# Production_Solar_Array_Design.net
KiCad netlist of a schematic drawn in EAGLE
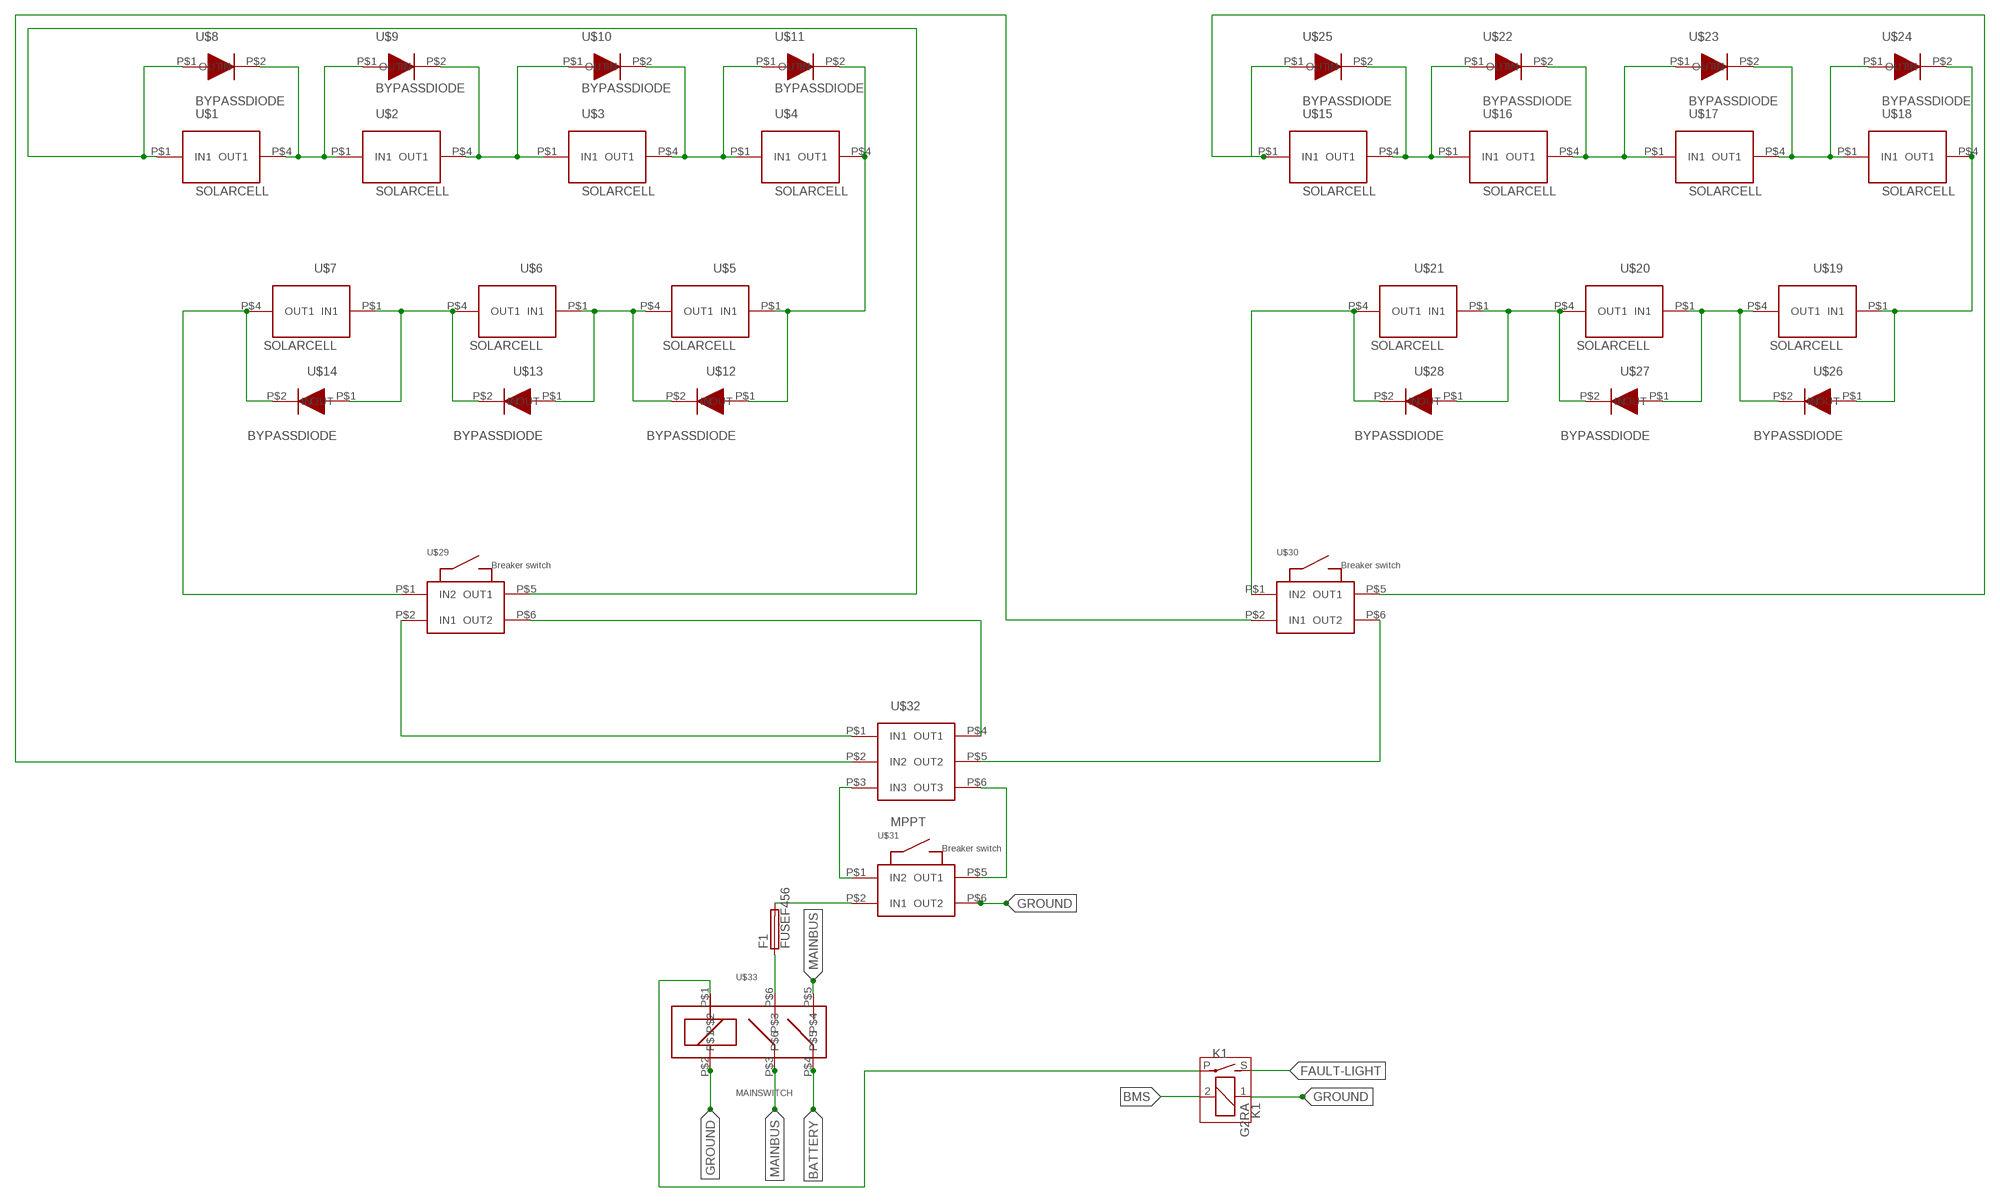
[diagram p0: schematic, sheet 1]

(export (version "E")
  (design (tool "Eeschema 10.0.6"))
  (components
    (comp (ref "F1")
      (value "FUSEF456")
      (footprint "eagle-import:F456")
      (libsource (lib "eagle-import") (part "FUSEF456"))
    )
    (comp (ref "K1")
      (value "G2RA")
      (footprint "eagle-import:G2RA")
      (libsource (lib "eagle-import") (part "G2RA"))
    )
    (comp (ref "U$1")
      (value "SOLARCELL")
      (footprint "eagle-import:SOLARCELL")
      (libsource (lib "eagle-import") (part "SOLARCELL"))
    )
    (comp (ref "U$2")
      (value "SOLARCELL")
      (footprint "eagle-import:SOLARCELL")
      (libsource (lib "eagle-import") (part "SOLARCELL"))
    )
    (comp (ref "U$3")
      (value "SOLARCELL")
      (footprint "eagle-import:SOLARCELL")
      (libsource (lib "eagle-import") (part "SOLARCELL"))
    )
    (comp (ref "U$4")
      (value "SOLARCELL")
      (footprint "eagle-import:SOLARCELL")
      (libsource (lib "eagle-import") (part "SOLARCELL"))
    )
    (comp (ref "U$5")
      (value "SOLARCELL")
      (footprint "eagle-import:SOLARCELL")
      (libsource (lib "eagle-import") (part "SOLARCELL"))
    )
    (comp (ref "U$6")
      (value "SOLARCELL")
      (footprint "eagle-import:SOLARCELL")
      (libsource (lib "eagle-import") (part "SOLARCELL"))
    )
    (comp (ref "U$7")
      (value "SOLARCELL")
      (footprint "eagle-import:SOLARCELL")
      (libsource (lib "eagle-import") (part "SOLARCELL"))
    )
    (comp (ref "U$8")
      (value "BYPASSDIODE")
      (footprint "eagle-import:BYPASSDIODE")
      (libsource (lib "eagle-import") (part "BYPASSDIODE"))
    )
    (comp (ref "U$9")
      (value "BYPASSDIODE")
      (footprint "eagle-import:BYPASSDIODE")
      (libsource (lib "eagle-import") (part "BYPASSDIODE"))
    )
    (comp (ref "U$10")
      (value "BYPASSDIODE")
      (footprint "eagle-import:BYPASSDIODE")
      (libsource (lib "eagle-import") (part "BYPASSDIODE"))
    )
    (comp (ref "U$11")
      (value "BYPASSDIODE")
      (footprint "eagle-import:BYPASSDIODE")
      (libsource (lib "eagle-import") (part "BYPASSDIODE"))
    )
    (comp (ref "U$12")
      (value "BYPASSDIODE")
      (footprint "eagle-import:BYPASSDIODE")
      (libsource (lib "eagle-import") (part "BYPASSDIODE"))
    )
    (comp (ref "U$13")
      (value "BYPASSDIODE")
      (footprint "eagle-import:BYPASSDIODE")
      (libsource (lib "eagle-import") (part "BYPASSDIODE"))
    )
    (comp (ref "U$14")
      (value "BYPASSDIODE")
      (footprint "eagle-import:BYPASSDIODE")
      (libsource (lib "eagle-import") (part "BYPASSDIODE"))
    )
    (comp (ref "U$15")
      (value "SOLARCELL")
      (footprint "eagle-import:SOLARCELL")
      (libsource (lib "eagle-import") (part "SOLARCELL"))
    )
    (comp (ref "U$16")
      (value "SOLARCELL")
      (footprint "eagle-import:SOLARCELL")
      (libsource (lib "eagle-import") (part "SOLARCELL"))
    )
    (comp (ref "U$17")
      (value "SOLARCELL")
      (footprint "eagle-import:SOLARCELL")
      (libsource (lib "eagle-import") (part "SOLARCELL"))
    )
    (comp (ref "U$18")
      (value "SOLARCELL")
      (footprint "eagle-import:SOLARCELL")
      (libsource (lib "eagle-import") (part "SOLARCELL"))
    )
    (comp (ref "U$19")
      (value "SOLARCELL")
      (footprint "eagle-import:SOLARCELL")
      (libsource (lib "eagle-import") (part "SOLARCELL"))
    )
    (comp (ref "U$20")
      (value "SOLARCELL")
      (footprint "eagle-import:SOLARCELL")
      (libsource (lib "eagle-import") (part "SOLARCELL"))
    )
    (comp (ref "U$21")
      (value "SOLARCELL")
      (footprint "eagle-import:SOLARCELL")
      (libsource (lib "eagle-import") (part "SOLARCELL"))
    )
    (comp (ref "U$22")
      (value "BYPASSDIODE")
      (footprint "eagle-import:BYPASSDIODE")
      (libsource (lib "eagle-import") (part "BYPASSDIODE"))
    )
    (comp (ref "U$23")
      (value "BYPASSDIODE")
      (footprint "eagle-import:BYPASSDIODE")
      (libsource (lib "eagle-import") (part "BYPASSDIODE"))
    )
    (comp (ref "U$24")
      (value "BYPASSDIODE")
      (footprint "eagle-import:BYPASSDIODE")
      (libsource (lib "eagle-import") (part "BYPASSDIODE"))
    )
    (comp (ref "U$25")
      (value "BYPASSDIODE")
      (footprint "eagle-import:BYPASSDIODE")
      (libsource (lib "eagle-import") (part "BYPASSDIODE"))
    )
    (comp (ref "U$26")
      (value "BYPASSDIODE")
      (footprint "eagle-import:BYPASSDIODE")
      (libsource (lib "eagle-import") (part "BYPASSDIODE"))
    )
    (comp (ref "U$27")
      (value "BYPASSDIODE")
      (footprint "eagle-import:BYPASSDIODE")
      (libsource (lib "eagle-import") (part "BYPASSDIODE"))
    )
    (comp (ref "U$28")
      (value "BYPASSDIODE")
      (footprint "eagle-import:BYPASSDIODE")
      (libsource (lib "eagle-import") (part "BYPASSDIODE"))
    )
    (comp (ref "U$29")
      (value "CIRCUITBREAKER")
      (footprint "eagle-import:CIRUITBREAKER")
      (libsource (lib "eagle-import") (part "CIRCUITBREAKER"))
    )
    (comp (ref "U$30")
      (value "CIRCUITBREAKER")
      (footprint "eagle-import:CIRUITBREAKER")
      (libsource (lib "eagle-import") (part "CIRCUITBREAKER"))
    )
    (comp (ref "U$31")
      (value "CIRCUITBREAKER")
      (footprint "eagle-import:CIRUITBREAKER")
      (libsource (lib "eagle-import") (part "CIRCUITBREAKER"))
    )
    (comp (ref "U$32")
      (value "MPPT")
      (footprint "eagle-import:MPPT")
      (libsource (lib "eagle-import") (part "MPPT"))
    )
    (comp (ref "U$33")
      (value "MAINSWITCH")
      (footprint "eagle-import:MAINSWITCH")
      (libsource (lib "eagle-import") (part "MAINSWITCH"))
    )
  )
  (nets
    (net (code "1") (name "BATTERY") (class "Default")
      (node (ref "U$33") (pin "P$4") (pinfunction "P$4_P$4") (pintype "bidirectional"))
    )
    (net (code "2") (name "BMS") (class "Default")
      (node (ref "K1") (pin "2") (pinfunction "2_2") (pintype "passive"))
    )
    (net (code "3") (name "FAULT-LIGHT") (class "Default")
      (node (ref "K1") (pin "S") (pinfunction "S_S") (pintype "passive"))
    )
    (net (code "4") (name "GROUND") (class "Default")
      (node (ref "K1") (pin "1") (pinfunction "1_1") (pintype "passive"))
      (node (ref "U$31") (pin "P$6") (pinfunction "OUT2_P$6") (pintype "bidirectional"))
      (node (ref "U$33") (pin "P$2") (pinfunction "P$2_P$2") (pintype "bidirectional"))
    )
    (net (code "5") (name "MAINBUS") (class "Default")
      (node (ref "U$33") (pin "P$3") (pinfunction "P$3_P$3") (pintype "bidirectional"))
      (node (ref "U$33") (pin "P$5") (pinfunction "P$5_P$5") (pintype "bidirectional"))
    )
    (net (code "6") (name "Net-(F1-Pad1)") (class "Default")
      (node (ref "F1") (pin "1") (pinfunction "1_1") (pintype "passive"))
      (node (ref "U$33") (pin "P$6") (pinfunction "P$6_P$6") (pintype "bidirectional"))
    )
    (net (code "7") (name "Net-(K1-PadP)") (class "Default")
      (node (ref "K1") (pin "P") (pinfunction "P_P") (pintype "passive"))
      (node (ref "U$33") (pin "P$1") (pinfunction "P$1_P$1") (pintype "bidirectional"))
    )
    (net (code "8") (name "Net-(U$1-IN1)") (class "Default")
      (node (ref "U$1") (pin "P$1") (pinfunction "IN1_P$1") (pintype "bidirectional"))
      (node (ref "U$29") (pin "P$5") (pinfunction "OUT1_P$5") (pintype "bidirectional"))
      (node (ref "U$8") (pin "P$1") (pinfunction "IN_P$1") (pintype "bidirectional"))
    )
    (net (code "9") (name "Net-(U$1-OUT1)") (class "Default")
      (node (ref "U$1") (pin "P$4") (pinfunction "OUT1_P$4") (pintype "bidirectional"))
      (node (ref "U$2") (pin "P$1") (pinfunction "IN1_P$1") (pintype "bidirectional"))
      (node (ref "U$8") (pin "P$2") (pinfunction "OUT_P$2") (pintype "bidirectional"))
      (node (ref "U$9") (pin "P$1") (pinfunction "IN_P$1") (pintype "bidirectional"))
    )
    (net (code "10") (name "Net-(U$10-IN)") (class "Default")
      (node (ref "U$10") (pin "P$1") (pinfunction "IN_P$1") (pintype "bidirectional"))
      (node (ref "U$2") (pin "P$4") (pinfunction "OUT1_P$4") (pintype "bidirectional"))
      (node (ref "U$3") (pin "P$1") (pinfunction "IN1_P$1") (pintype "bidirectional"))
      (node (ref "U$9") (pin "P$2") (pinfunction "OUT_P$2") (pintype "bidirectional"))
    )
    (net (code "11") (name "Net-(U$10-OUT)") (class "Default")
      (node (ref "U$10") (pin "P$2") (pinfunction "OUT_P$2") (pintype "bidirectional"))
      (node (ref "U$11") (pin "P$1") (pinfunction "IN_P$1") (pintype "bidirectional"))
      (node (ref "U$3") (pin "P$4") (pinfunction "OUT1_P$4") (pintype "bidirectional"))
      (node (ref "U$4") (pin "P$1") (pinfunction "IN1_P$1") (pintype "bidirectional"))
    )
    (net (code "12") (name "Net-(U$11-OUT)") (class "Default")
      (node (ref "U$11") (pin "P$2") (pinfunction "OUT_P$2") (pintype "bidirectional"))
      (node (ref "U$12") (pin "P$1") (pinfunction "IN_P$1") (pintype "bidirectional"))
      (node (ref "U$4") (pin "P$4") (pinfunction "OUT1_P$4") (pintype "bidirectional"))
      (node (ref "U$5") (pin "P$1") (pinfunction "IN1_P$1") (pintype "bidirectional"))
    )
    (net (code "13") (name "Net-(U$12-OUT)") (class "Default")
      (node (ref "U$12") (pin "P$2") (pinfunction "OUT_P$2") (pintype "bidirectional"))
      (node (ref "U$13") (pin "P$1") (pinfunction "IN_P$1") (pintype "bidirectional"))
      (node (ref "U$5") (pin "P$4") (pinfunction "OUT1_P$4") (pintype "bidirectional"))
      (node (ref "U$6") (pin "P$1") (pinfunction "IN1_P$1") (pintype "bidirectional"))
    )
    (net (code "14") (name "Net-(U$13-OUT)") (class "Default")
      (node (ref "U$13") (pin "P$2") (pinfunction "OUT_P$2") (pintype "bidirectional"))
      (node (ref "U$14") (pin "P$1") (pinfunction "IN_P$1") (pintype "bidirectional"))
      (node (ref "U$6") (pin "P$4") (pinfunction "OUT1_P$4") (pintype "bidirectional"))
      (node (ref "U$7") (pin "P$1") (pinfunction "IN1_P$1") (pintype "bidirectional"))
    )
    (net (code "15") (name "Net-(U$14-OUT)") (class "Default")
      (node (ref "U$14") (pin "P$2") (pinfunction "OUT_P$2") (pintype "bidirectional"))
      (node (ref "U$29") (pin "P$1") (pinfunction "IN2_P$1") (pintype "bidirectional"))
      (node (ref "U$7") (pin "P$4") (pinfunction "OUT1_P$4") (pintype "bidirectional"))
    )
    (net (code "16") (name "Net-(U$15-IN1)") (class "Default")
      (node (ref "U$15") (pin "P$1") (pinfunction "IN1_P$1") (pintype "bidirectional"))
      (node (ref "U$25") (pin "P$1") (pinfunction "IN_P$1") (pintype "bidirectional"))
      (node (ref "U$30") (pin "P$5") (pinfunction "OUT1_P$5") (pintype "bidirectional"))
    )
    (net (code "17") (name "Net-(U$15-OUT1)") (class "Default")
      (node (ref "U$15") (pin "P$4") (pinfunction "OUT1_P$4") (pintype "bidirectional"))
      (node (ref "U$16") (pin "P$1") (pinfunction "IN1_P$1") (pintype "bidirectional"))
      (node (ref "U$22") (pin "P$1") (pinfunction "IN_P$1") (pintype "bidirectional"))
      (node (ref "U$25") (pin "P$2") (pinfunction "OUT_P$2") (pintype "bidirectional"))
    )
    (net (code "18") (name "Net-(U$16-OUT1)") (class "Default")
      (node (ref "U$16") (pin "P$4") (pinfunction "OUT1_P$4") (pintype "bidirectional"))
      (node (ref "U$17") (pin "P$1") (pinfunction "IN1_P$1") (pintype "bidirectional"))
      (node (ref "U$22") (pin "P$2") (pinfunction "OUT_P$2") (pintype "bidirectional"))
      (node (ref "U$23") (pin "P$1") (pinfunction "IN_P$1") (pintype "bidirectional"))
    )
    (net (code "19") (name "Net-(U$17-OUT1)") (class "Default")
      (node (ref "U$17") (pin "P$4") (pinfunction "OUT1_P$4") (pintype "bidirectional"))
      (node (ref "U$18") (pin "P$1") (pinfunction "IN1_P$1") (pintype "bidirectional"))
      (node (ref "U$23") (pin "P$2") (pinfunction "OUT_P$2") (pintype "bidirectional"))
      (node (ref "U$24") (pin "P$1") (pinfunction "IN_P$1") (pintype "bidirectional"))
    )
    (net (code "20") (name "Net-(U$18-OUT1)") (class "Default")
      (node (ref "U$18") (pin "P$4") (pinfunction "OUT1_P$4") (pintype "bidirectional"))
      (node (ref "U$19") (pin "P$1") (pinfunction "IN1_P$1") (pintype "bidirectional"))
      (node (ref "U$24") (pin "P$2") (pinfunction "OUT_P$2") (pintype "bidirectional"))
      (node (ref "U$26") (pin "P$1") (pinfunction "IN_P$1") (pintype "bidirectional"))
    )
    (net (code "21") (name "Net-(U$19-OUT1)") (class "Default")
      (node (ref "U$19") (pin "P$4") (pinfunction "OUT1_P$4") (pintype "bidirectional"))
      (node (ref "U$20") (pin "P$1") (pinfunction "IN1_P$1") (pintype "bidirectional"))
      (node (ref "U$26") (pin "P$2") (pinfunction "OUT_P$2") (pintype "bidirectional"))
      (node (ref "U$27") (pin "P$1") (pinfunction "IN_P$1") (pintype "bidirectional"))
    )
    (net (code "22") (name "Net-(U$20-OUT1)") (class "Default")
      (node (ref "U$20") (pin "P$4") (pinfunction "OUT1_P$4") (pintype "bidirectional"))
      (node (ref "U$21") (pin "P$1") (pinfunction "IN1_P$1") (pintype "bidirectional"))
      (node (ref "U$27") (pin "P$2") (pinfunction "OUT_P$2") (pintype "bidirectional"))
      (node (ref "U$28") (pin "P$1") (pinfunction "IN_P$1") (pintype "bidirectional"))
    )
    (net (code "23") (name "Net-(U$21-OUT1)") (class "Default")
      (node (ref "U$21") (pin "P$4") (pinfunction "OUT1_P$4") (pintype "bidirectional"))
      (node (ref "U$28") (pin "P$2") (pinfunction "OUT_P$2") (pintype "bidirectional"))
      (node (ref "U$30") (pin "P$1") (pinfunction "IN2_P$1") (pintype "bidirectional"))
    )
    (net (code "24") (name "Net-(U$29-IN1)") (class "Default")
      (node (ref "U$29") (pin "P$2") (pinfunction "IN1_P$2") (pintype "bidirectional"))
      (node (ref "U$32") (pin "P$1") (pinfunction "IN1_P$1") (pintype "bidirectional"))
    )
    (net (code "25") (name "Net-(U$29-OUT2)") (class "Default")
      (node (ref "U$29") (pin "P$6") (pinfunction "OUT2_P$6") (pintype "bidirectional"))
      (node (ref "U$32") (pin "P$4") (pinfunction "OUT1_P$4") (pintype "bidirectional"))
    )
    (net (code "26") (name "Net-(U$30-IN1)") (class "Default")
      (node (ref "U$30") (pin "P$2") (pinfunction "IN1_P$2") (pintype "bidirectional"))
      (node (ref "U$32") (pin "P$2") (pinfunction "IN2_P$2") (pintype "bidirectional"))
    )
    (net (code "27") (name "Net-(U$30-OUT2)") (class "Default")
      (node (ref "U$30") (pin "P$6") (pinfunction "OUT2_P$6") (pintype "bidirectional"))
      (node (ref "U$32") (pin "P$5") (pinfunction "OUT2_P$5") (pintype "bidirectional"))
    )
    (net (code "28") (name "Net-(U$31-IN1)") (class "Default")
      (node (ref "F1") (pin "2") (pinfunction "2_2") (pintype "passive"))
      (node (ref "U$31") (pin "P$2") (pinfunction "IN1_P$2") (pintype "bidirectional"))
    )
    (net (code "29") (name "Net-(U$31-IN2)") (class "Default")
      (node (ref "U$31") (pin "P$1") (pinfunction "IN2_P$1") (pintype "bidirectional"))
      (node (ref "U$32") (pin "P$3") (pinfunction "IN3_P$3") (pintype "bidirectional"))
    )
    (net (code "30") (name "Net-(U$31-OUT1)") (class "Default")
      (node (ref "U$31") (pin "P$5") (pinfunction "OUT1_P$5") (pintype "bidirectional"))
      (node (ref "U$32") (pin "P$6") (pinfunction "OUT3_P$6") (pintype "bidirectional"))
    )
  )
)
